# BLE_TORQUE.net
KiCad netlist of a schematic drawn in Altium Designer
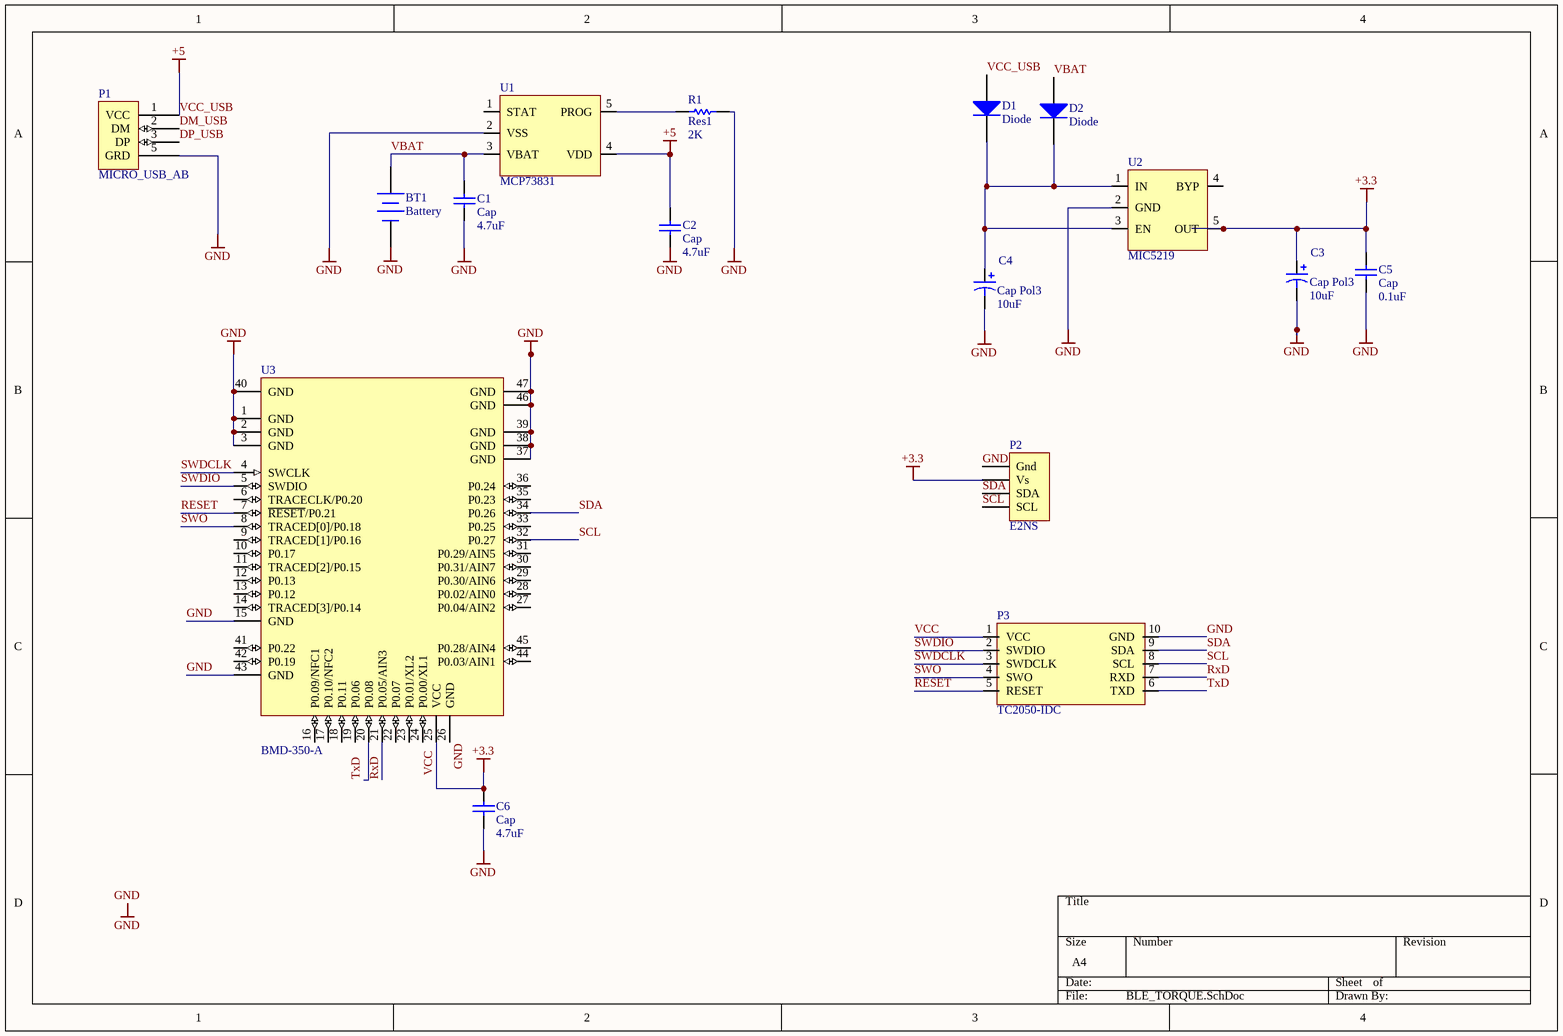
[diagram p0: BLE_TORQUE.SchDoc]

(export (version "E")
  (design (tool "Eeschema 10.0.6"))
  (components
    (comp (ref "BT1")
      (value "Battery")
      (footprint "BAT-2")
      (description "Multicell Battery")
      (fields (field (name "PUBLISHER") "Altium Limited"))
      (libsource (lib "Miscellaneous Devices") (part "Battery"))
    )
    (comp (ref "C1")
      (value "Cap")
      (footprint "C0805")
      (description "Capacitor")
      (fields (field (name "ALTIUM_VALUE") "4.7uF") (field (name "PUBLISHER") "Altium Limited"))
      (libsource (lib "Miscellaneous Devices") (part "Cap"))
    )
    (comp (ref "C2")
      (value "Cap")
      (footprint "C0805")
      (description "Capacitor")
      (fields (field (name "ALTIUM_VALUE") "4.7uF") (field (name "PUBLISHER") "Altium Limited"))
      (libsource (lib "Miscellaneous Devices") (part "Cap"))
    )
    (comp (ref "C3")
      (value "Cap Pol3")
      (footprint "C0805")
      (description "Polarized Capacitor (Surface Mount)")
      (fields (field (name "ALTIUM_VALUE") "10uF") (field (name "PUBLISHER") "Altium Limited"))
      (libsource (lib "Miscellaneous Devices") (part "Cap Pol3"))
    )
    (comp (ref "C4")
      (value "Cap Pol3")
      (footprint "C0805")
      (description "Polarized Capacitor (Surface Mount)")
      (fields (field (name "ALTIUM_VALUE") "10uF") (field (name "PUBLISHER") "Altium Limited"))
      (libsource (lib "Miscellaneous Devices") (part "Cap Pol3"))
    )
    (comp (ref "C5")
      (value "Cap")
      (footprint "C0805")
      (description "Capacitor")
      (fields (field (name "ALTIUM_VALUE") "0.1uF") (field (name "PUBLISHER") "Altium Limited"))
      (libsource (lib "Miscellaneous Devices") (part "Cap"))
    )
    (comp (ref "C6")
      (value "Cap")
      (footprint "C0805")
      (description "Capacitor")
      (fields (field (name "ALTIUM_VALUE") "4.7uF") (field (name "PUBLISHER") "Altium Limited"))
      (libsource (lib "Miscellaneous Devices") (part "Cap"))
    )
    (comp (ref "D1")
      (value "Diode")
      (footprint "SMB")
      (description "Default Diode")
      (fields (field (name "PUBLISHER") "Altium Limited"))
      (libsource (lib "Miscellaneous Devices") (part "Diode"))
    )
    (comp (ref "D2")
      (value "Diode")
      (footprint "SMB")
      (description "Default Diode")
      (fields (field (name "PUBLISHER") "Altium Limited"))
      (libsource (lib "Miscellaneous Devices") (part "Diode"))
    )
    (comp (ref "P1")
      (value "MICRO_USB_AB")
      (footprint "MICRO_USB_AB")
      (libsource (lib "MICROUSB") (part "MICRO_USB_AB"))
    )
    (comp (ref "P2")
      (value "E2NS")
      (footprint "HDR1X4")
      (description "Header, 4-Pin")
      (fields (field (name "PUBLISHER") "Altium Limited"))
      (libsource (lib "Miscellaneous Connectors") (part "Header 4"))
    )
    (comp (ref "P3")
      (value "TC2050-IDC")
      (footprint "TC2050-IDC")
      (libsource (lib "TC2050-IDC-09Mar2012") (part "TC2050-IDC"))
    )
    (comp (ref "R1")
      (value "Res1")
      (footprint "C0805")
      (description "Resistor")
      (fields (field (name "ALTIUM_VALUE") "2K") (field (name "PUBLISHER") "Altium Limited"))
      (libsource (lib "Miscellaneous Devices") (part "Res1"))
    )
    (comp (ref "U1") (value "MCP73831") (footprint "SOT-23-5") (libsource (lib "MCP73831") (part "MCP73831")))
    (comp (ref "U2") (value "MIC5219") (footprint "SOT-23-5") (libsource (lib "mic5219") (part "MIC5219")))
    (comp (ref "U3")
      (value "BMD-350-A")
      (footprint "BMD-350")
      (description "Bluetooth 4.2 LE Module, nRF52832, 512kB Flash, 64kB RAM")
      (fields
        (field (name "MANUFACTURER") "Rigado")
        (field (name "PART NUMBER") "BMD-350-A")
        (field (name "ADDED BY") "Cam N")
      )
      (libsource (lib "BMD-350") (part "BMD-350"))
    )
  )
  (nets
    (net (code "1") (name "+3.3") (class "Default")
      (node (ref "C3") (pin "1") (pinfunction "1_1") (pintype "passive"))
      (node (ref "C5") (pin "1") (pinfunction "1_1") (pintype "passive"))
      (node (ref "C6") (pin "1") (pinfunction "1_1") (pintype "passive"))
      (node (ref "P2") (pin "2") (pinfunction "Vs_2") (pintype "passive"))
      (node (ref "P3") (pin "1") (pinfunction "VCC_1") (pintype "passive"))
      (node (ref "U2") (pin "5") (pinfunction "OUT_5") (pintype "passive"))
      (node (ref "U3") (pin "25") (pinfunction "VCC_25") (pintype "power_in"))
    )
    (net (code "2") (name "+5") (class "Default")
      (node (ref "C2") (pin "1") (pinfunction "1_1") (pintype "passive"))
      (node (ref "D1") (pin "1") (pinfunction "A_1") (pintype "passive"))
      (node (ref "P1") (pin "1") (pinfunction "VCC_1") (pintype "power_in"))
      (node (ref "U1") (pin "4") (pinfunction "VDD_4") (pintype "passive"))
    )
    (net (code "3") (name "/DM_USB") (class "Default")
      (node (ref "P1") (pin "2") (pinfunction "DM_2") (pintype "bidirectional"))
    )
    (net (code "4") (name "/DP_USB") (class "Default")
      (node (ref "P1") (pin "3") (pinfunction "DP_3") (pintype "bidirectional"))
    )
    (net (code "5") (name "/RESET") (class "Default")
      (node (ref "P3") (pin "5") (pinfunction "RESET_5") (pintype "passive"))
      (node (ref "U3") (pin "7") (pinfunction "~{RESET}/P0.21_7") (pintype "bidirectional"))
    )
    (net (code "6") (name "/RxD") (class "Default")
      (node (ref "P3") (pin "7") (pinfunction "RXD_7") (pintype "passive"))
      (node (ref "U3") (pin "21") (pinfunction "P0.05/AIN3_21") (pintype "bidirectional"))
    )
    (net (code "7") (name "/SCL") (class "Default")
      (node (ref "P2") (pin "4") (pinfunction "SCL_4") (pintype "passive"))
      (node (ref "P3") (pin "8") (pinfunction "SCL_8") (pintype "passive"))
      (node (ref "U3") (pin "32") (pinfunction "P0.27_32") (pintype "bidirectional"))
    )
    (net (code "8") (name "/SDA") (class "Default")
      (node (ref "P2") (pin "3") (pinfunction "SDA_3") (pintype "passive"))
      (node (ref "P3") (pin "9") (pinfunction "SDA_9") (pintype "passive"))
      (node (ref "U3") (pin "34") (pinfunction "P0.26_34") (pintype "bidirectional"))
    )
    (net (code "9") (name "/SWDCLK") (class "Default")
      (node (ref "P3") (pin "3") (pinfunction "SWDCLK_3") (pintype "passive"))
      (node (ref "U3") (pin "4") (pinfunction "SWCLK_4") (pintype "input"))
    )
    (net (code "10") (name "/SWDIO") (class "Default")
      (node (ref "P3") (pin "2") (pinfunction "SWDIO_2") (pintype "passive"))
      (node (ref "U3") (pin "5") (pinfunction "SWDIO_5") (pintype "bidirectional"))
    )
    (net (code "11") (name "/SWO") (class "Default")
      (node (ref "P3") (pin "4") (pinfunction "SWO_4") (pintype "passive"))
      (node (ref "U3") (pin "8") (pinfunction "TRACED[0]/P0.18_8") (pintype "bidirectional"))
    )
    (net (code "12") (name "/TxD") (class "Default")
      (node (ref "P3") (pin "6") (pinfunction "TXD_6") (pintype "passive"))
      (node (ref "U3") (pin "20") (pinfunction "P0.08_20") (pintype "bidirectional"))
    )
    (net (code "13") (name "/VBAT") (class "Default")
      (node (ref "BT1") (pin "1") (pinfunction "+_1") (pintype "passive"))
      (node (ref "C1") (pin "1") (pinfunction "1_1") (pintype "passive"))
      (node (ref "D2") (pin "1") (pinfunction "A_1") (pintype "passive"))
      (node (ref "U1") (pin "3") (pinfunction "VBAT_3") (pintype "passive"))
    )
    (net (code "14") (name "GND") (class "Default")
      (node (ref "BT1") (pin "2") (pinfunction "-_2") (pintype "passive"))
      (node (ref "C1") (pin "2") (pinfunction "2_2") (pintype "passive"))
      (node (ref "C2") (pin "2") (pinfunction "2_2") (pintype "passive"))
      (node (ref "C3") (pin "2") (pinfunction "2_2") (pintype "passive"))
      (node (ref "C4") (pin "2") (pinfunction "2_2") (pintype "passive"))
      (node (ref "C5") (pin "2") (pinfunction "2_2") (pintype "passive"))
      (node (ref "C6") (pin "2") (pinfunction "2_2") (pintype "passive"))
      (node (ref "P1") (pin "5") (pinfunction "GRD_5") (pintype "power_in"))
      (node (ref "P2") (pin "1") (pinfunction "Gnd_1") (pintype "passive"))
      (node (ref "P3") (pin "10") (pinfunction "GND_10") (pintype "passive"))
      (node (ref "R1") (pin "2") (pinfunction "2_2") (pintype "passive"))
      (node (ref "U1") (pin "2") (pinfunction "VSS_2") (pintype "passive"))
      (node (ref "U2") (pin "2") (pinfunction "GND_2") (pintype "passive"))
      (node (ref "U3") (pin "1") (pinfunction "GND_1") (pintype "power_in"))
      (node (ref "U3") (pin "15") (pinfunction "GND_15") (pintype "power_in"))
      (node (ref "U3") (pin "2") (pinfunction "GND_2") (pintype "power_in"))
      (node (ref "U3") (pin "26") (pinfunction "GND_26") (pintype "power_in"))
      (node (ref "U3") (pin "3") (pinfunction "GND_3") (pintype "power_in"))
      (node (ref "U3") (pin "37") (pinfunction "GND_37") (pintype "power_in"))
      (node (ref "U3") (pin "38") (pinfunction "GND_38") (pintype "power_in"))
      (node (ref "U3") (pin "39") (pinfunction "GND_39") (pintype "power_in"))
      (node (ref "U3") (pin "40") (pinfunction "GND_40") (pintype "power_in"))
      (node (ref "U3") (pin "43") (pinfunction "GND_43") (pintype "power_in"))
      (node (ref "U3") (pin "46") (pinfunction "GND_46") (pintype "power_in"))
      (node (ref "U3") (pin "47") (pinfunction "GND_47") (pintype "power_in"))
    )
    (net (code "15") (name "Net-(D1-K)") (class "Default")
      (node (ref "C4") (pin "1") (pinfunction "1_1") (pintype "passive"))
      (node (ref "D1") (pin "2") (pinfunction "K_2") (pintype "passive"))
      (node (ref "D2") (pin "2") (pinfunction "K_2") (pintype "passive"))
      (node (ref "U2") (pin "1") (pinfunction "IN_1") (pintype "passive"))
      (node (ref "U2") (pin "3") (pinfunction "EN_3") (pintype "passive"))
    )
    (net (code "16") (name "Net-(U1-PROG)") (class "Default")
      (node (ref "R1") (pin "1") (pinfunction "1_1") (pintype "passive"))
      (node (ref "U1") (pin "5") (pinfunction "PROG_5") (pintype "passive"))
    )
    (net (code "17") (name "unconnected-(U1-STAT-Pad1)") (class "Default")
      (node (ref "U1") (pin "1") (pinfunction "STAT_1") (pintype "passive"))
    )
    (net (code "18") (name "unconnected-(U2-BYP-Pad4)") (class "Default")
      (node (ref "U2") (pin "4") (pinfunction "BYP_4") (pintype "passive"))
    )
    (net (code "19") (name "unconnected-(U3-P0.00{slash}XL1-Pad24)") (class "Default")
      (node (ref "U3") (pin "24") (pinfunction "P0.00/XL1_24") (pintype "bidirectional"))
    )
    (net (code "20") (name "unconnected-(U3-P0.01{slash}XL2-Pad23)") (class "Default")
      (node (ref "U3") (pin "23") (pinfunction "P0.01/XL2_23") (pintype "bidirectional"))
    )
    (net (code "21") (name "unconnected-(U3-P0.02{slash}AIN0-Pad28)") (class "Default")
      (node (ref "U3") (pin "28") (pinfunction "P0.02/AIN0_28") (pintype "bidirectional"))
    )
    (net (code "22") (name "unconnected-(U3-P0.03{slash}AIN1-Pad44)") (class "Default")
      (node (ref "U3") (pin "44") (pinfunction "P0.03/AIN1_44") (pintype "bidirectional"))
    )
    (net (code "23") (name "unconnected-(U3-P0.04{slash}AIN2-Pad27)") (class "Default")
      (node (ref "U3") (pin "27") (pinfunction "P0.04/AIN2_27") (pintype "bidirectional"))
    )
    (net (code "24") (name "unconnected-(U3-P0.06-Pad19)") (class "Default")
      (node (ref "U3") (pin "19") (pinfunction "P0.06_19") (pintype "bidirectional"))
    )
    (net (code "25") (name "unconnected-(U3-P0.07-Pad22)") (class "Default")
      (node (ref "U3") (pin "22") (pinfunction "P0.07_22") (pintype "bidirectional"))
    )
    (net (code "26") (name "unconnected-(U3-P0.09{slash}NFC1-Pad16)") (class "Default")
      (node (ref "U3") (pin "16") (pinfunction "P0.09/NFC1_16") (pintype "bidirectional"))
    )
    (net (code "27") (name "unconnected-(U3-P0.10{slash}NFC2-Pad17)") (class "Default")
      (node (ref "U3") (pin "17") (pinfunction "P0.10/NFC2_17") (pintype "bidirectional"))
    )
    (net (code "28") (name "unconnected-(U3-P0.11-Pad18)") (class "Default")
      (node (ref "U3") (pin "18") (pinfunction "P0.11_18") (pintype "bidirectional"))
    )
    (net (code "29") (name "unconnected-(U3-P0.12-Pad13)") (class "Default")
      (node (ref "U3") (pin "13") (pinfunction "P0.12_13") (pintype "bidirectional"))
    )
    (net (code "30") (name "unconnected-(U3-P0.13-Pad12)") (class "Default")
      (node (ref "U3") (pin "12") (pinfunction "P0.13_12") (pintype "bidirectional"))
    )
    (net (code "31") (name "unconnected-(U3-P0.17-Pad10)") (class "Default")
      (node (ref "U3") (pin "10") (pinfunction "P0.17_10") (pintype "bidirectional"))
    )
    (net (code "32") (name "unconnected-(U3-P0.19-Pad42)") (class "Default")
      (node (ref "U3") (pin "42") (pinfunction "P0.19_42") (pintype "bidirectional"))
    )
    (net (code "33") (name "unconnected-(U3-P0.22-Pad41)") (class "Default")
      (node (ref "U3") (pin "41") (pinfunction "P0.22_41") (pintype "bidirectional"))
    )
    (net (code "34") (name "unconnected-(U3-P0.23-Pad35)") (class "Default")
      (node (ref "U3") (pin "35") (pinfunction "P0.23_35") (pintype "bidirectional"))
    )
    (net (code "35") (name "unconnected-(U3-P0.24-Pad36)") (class "Default")
      (node (ref "U3") (pin "36") (pinfunction "P0.24_36") (pintype "bidirectional"))
    )
    (net (code "36") (name "unconnected-(U3-P0.25-Pad33)") (class "Default")
      (node (ref "U3") (pin "33") (pinfunction "P0.25_33") (pintype "bidirectional"))
    )
    (net (code "37") (name "unconnected-(U3-P0.28{slash}AIN4-Pad45)") (class "Default")
      (node (ref "U3") (pin "45") (pinfunction "P0.28/AIN4_45") (pintype "bidirectional"))
    )
    (net (code "38") (name "unconnected-(U3-P0.29{slash}AIN5-Pad31)") (class "Default")
      (node (ref "U3") (pin "31") (pinfunction "P0.29/AIN5_31") (pintype "bidirectional"))
    )
    (net (code "39") (name "unconnected-(U3-P0.30{slash}AIN6-Pad29)") (class "Default")
      (node (ref "U3") (pin "29") (pinfunction "P0.30/AIN6_29") (pintype "bidirectional"))
    )
    (net (code "40") (name "unconnected-(U3-P0.31{slash}AIN7-Pad30)") (class "Default")
      (node (ref "U3") (pin "30") (pinfunction "P0.31/AIN7_30") (pintype "bidirectional"))
    )
    (net (code "41") (name "unconnected-(U3-TRACECLK{slash}P0.20-Pad6)") (class "Default")
      (node (ref "U3") (pin "6") (pinfunction "TRACECLK/P0.20_6") (pintype "bidirectional"))
    )
    (net (code "42") (name "unconnected-(U3-TRACED[1]{slash}P0.16-Pad9)") (class "Default")
      (node (ref "U3") (pin "9") (pinfunction "TRACED[1]/P0.16_9") (pintype "bidirectional"))
    )
    (net (code "43") (name "unconnected-(U3-TRACED[2]{slash}P0.15-Pad11)") (class "Default")
      (node (ref "U3") (pin "11") (pinfunction "TRACED[2]/P0.15_11") (pintype "bidirectional"))
    )
    (net (code "44") (name "unconnected-(U3-TRACED[3]{slash}P0.14-Pad14)") (class "Default")
      (node (ref "U3") (pin "14") (pinfunction "TRACED[3]/P0.14_14") (pintype "bidirectional"))
    )
  )
)
